# Sensors.net
KiCad netlist of a schematic drawn in Altium Designer
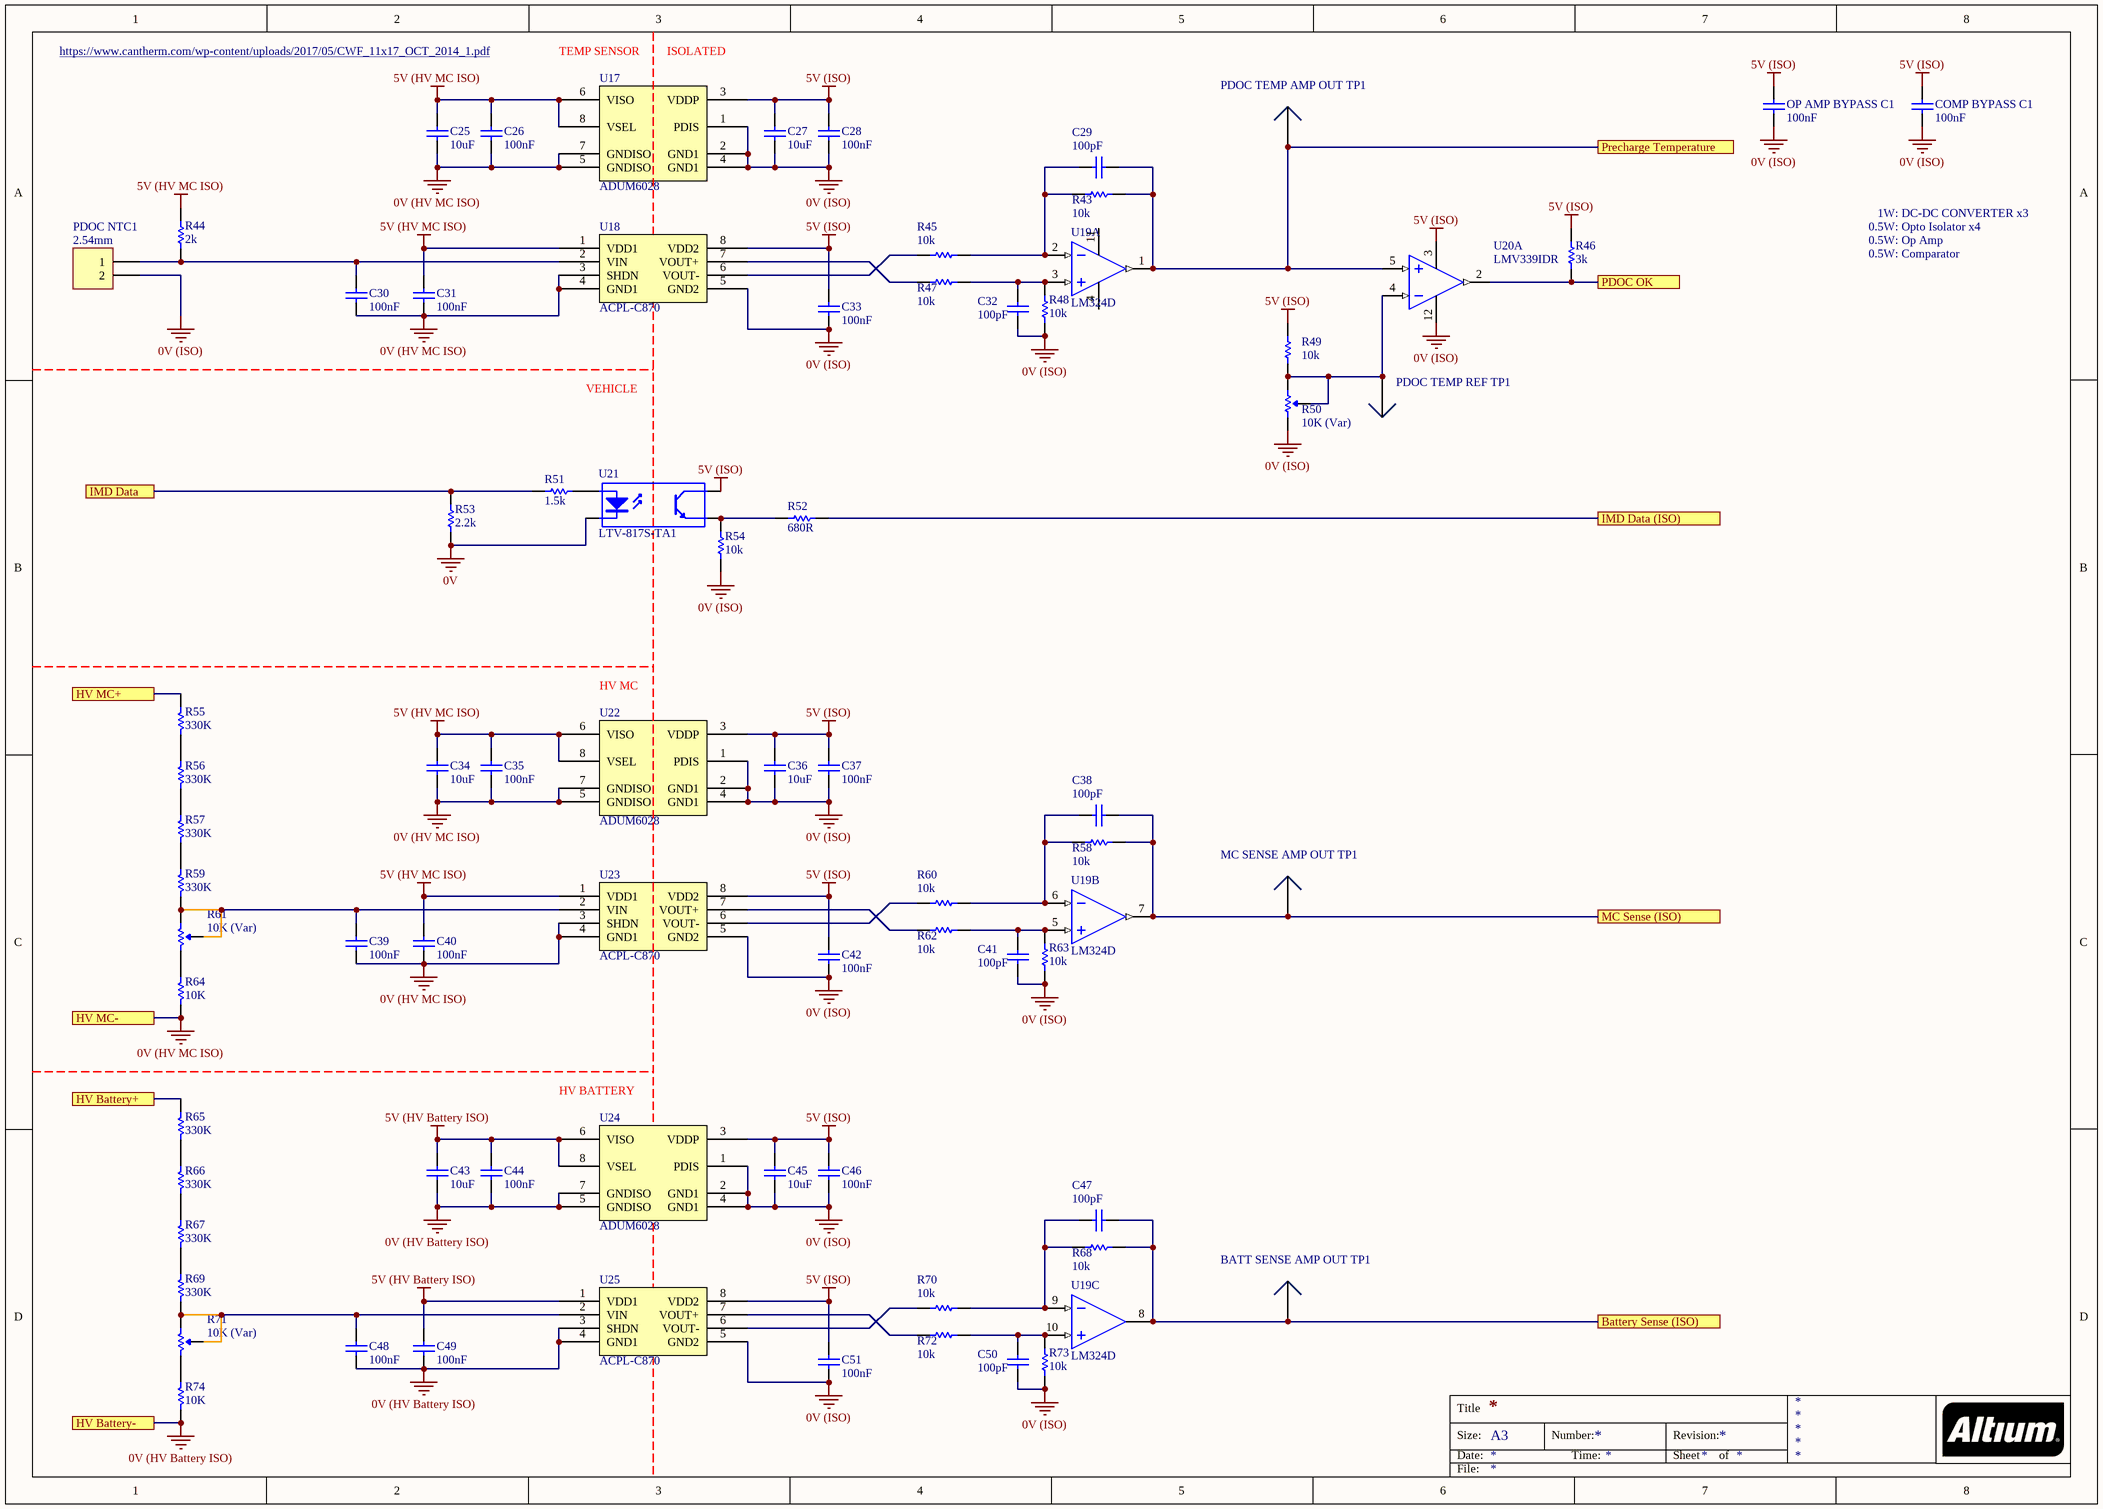
[diagram p0: Sensors.SchDoc]

(export (version "E")
  (design (tool "Eeschema 10.0.6"))
  (components
    (comp (ref "BATT SENSE AMP OUT TP1")
      (value "0mm")
      (footprint "SMD Test Point")
      (fields (field (name "PART NUMBER") "SMD Test Point") (field (name "CONTACT") "NA"))
      (libsource (lib "ts_20-standard-connectors") (part "Test Point"))
    )
    (comp (ref "C25")
      (value "10uF")
      (footprint "0805")
      (fields
        (field (name "PART NUMBER") "GRM21BR6YA106KE43L")
        (field (name "TOLERANCE") "10%")
        (field (name "MANUFACTURER") "muRata")
      )
      (libsource (lib "ts_20-standard-library") (part "Capacitor"))
    )
    (comp (ref "C26")
      (value "100nF")
      (footprint "0805")
      (fields
        (field (name "PART NUMBER") "GCM21BR71E104KA37L")
        (field (name "TOLERANCE") "10%")
        (field (name "MANUFACTURER") "muRata")
      )
      (libsource (lib "ts_20-standard-library") (part "Capacitor"))
    )
    (comp (ref "C27")
      (value "10uF")
      (footprint "0805")
      (fields
        (field (name "PART NUMBER") "GRM21BR6YA106KE43L")
        (field (name "TOLERANCE") "10%")
        (field (name "MANUFACTURER") "muRata")
      )
      (libsource (lib "ts_20-standard-library") (part "Capacitor"))
    )
    (comp (ref "C28")
      (value "100nF")
      (footprint "0805")
      (fields
        (field (name "PART NUMBER") "GCM21BR71E104KA37L")
        (field (name "TOLERANCE") "10%")
        (field (name "MANUFACTURER") "muRata")
      )
      (libsource (lib "ts_20-standard-library") (part "Capacitor"))
    )
    (comp (ref "C29")
      (value "100pF")
      (footprint "0805")
      (fields
        (field (name "PART NUMBER") "GCM21B5C1H101JA37L")
        (field (name "TOLERANCE") "5%")
        (field (name "MANUFACTURER") "muRata")
      )
      (libsource (lib "ts_20-standard-library") (part "Capacitor"))
    )
    (comp (ref "C30")
      (value "100nF")
      (footprint "0805")
      (fields
        (field (name "PART NUMBER") "GCM21BR71E104KA37L")
        (field (name "TOLERANCE") "10%")
        (field (name "MANUFACTURER") "muRata")
      )
      (libsource (lib "ts_20-standard-library") (part "Capacitor"))
    )
    (comp (ref "C31")
      (value "100nF")
      (footprint "0805")
      (fields
        (field (name "PART NUMBER") "GCM21BR71E104KA37L")
        (field (name "TOLERANCE") "10%")
        (field (name "MANUFACTURER") "muRata")
      )
      (libsource (lib "ts_20-standard-library") (part "Capacitor"))
    )
    (comp (ref "C32")
      (value "100pF")
      (footprint "0805")
      (fields
        (field (name "PART NUMBER") "GCM21B5C1H101JA37L")
        (field (name "TOLERANCE") "5%")
        (field (name "MANUFACTURER") "muRata")
      )
      (libsource (lib "ts_20-standard-library") (part "Capacitor"))
    )
    (comp (ref "C33")
      (value "100nF")
      (footprint "0805")
      (fields
        (field (name "PART NUMBER") "GCM21BR71E104KA37L")
        (field (name "TOLERANCE") "10%")
        (field (name "MANUFACTURER") "muRata")
      )
      (libsource (lib "ts_20-standard-library") (part "Capacitor"))
    )
    (comp (ref "C34")
      (value "10uF")
      (footprint "0805")
      (fields
        (field (name "PART NUMBER") "GRM21BR6YA106KE43L")
        (field (name "TOLERANCE") "10%")
        (field (name "MANUFACTURER") "muRata")
      )
      (libsource (lib "ts_20-standard-library") (part "Capacitor"))
    )
    (comp (ref "C35")
      (value "100nF")
      (footprint "0805")
      (fields
        (field (name "PART NUMBER") "GCM21BR71E104KA37L")
        (field (name "TOLERANCE") "10%")
        (field (name "MANUFACTURER") "muRata")
      )
      (libsource (lib "ts_20-standard-library") (part "Capacitor"))
    )
    (comp (ref "C36")
      (value "10uF")
      (footprint "0805")
      (fields
        (field (name "PART NUMBER") "GRM21BR6YA106KE43L")
        (field (name "TOLERANCE") "10%")
        (field (name "MANUFACTURER") "muRata")
      )
      (libsource (lib "ts_20-standard-library") (part "Capacitor"))
    )
    (comp (ref "C37")
      (value "100nF")
      (footprint "0805")
      (fields
        (field (name "PART NUMBER") "GCM21BR71E104KA37L")
        (field (name "TOLERANCE") "10%")
        (field (name "MANUFACTURER") "muRata")
      )
      (libsource (lib "ts_20-standard-library") (part "Capacitor"))
    )
    (comp (ref "C38")
      (value "100pF")
      (footprint "0805")
      (fields
        (field (name "PART NUMBER") "GCM21B5C1H101JA37L")
        (field (name "TOLERANCE") "5%")
        (field (name "MANUFACTURER") "muRata")
      )
      (libsource (lib "ts_20-standard-library") (part "Capacitor"))
    )
    (comp (ref "C39")
      (value "100nF")
      (footprint "0805")
      (fields
        (field (name "PART NUMBER") "GCM21BR71E104KA37L")
        (field (name "TOLERANCE") "10%")
        (field (name "MANUFACTURER") "muRata")
      )
      (libsource (lib "ts_20-standard-library") (part "Capacitor"))
    )
    (comp (ref "C40")
      (value "100nF")
      (footprint "0805")
      (fields
        (field (name "PART NUMBER") "GCM21BR71E104KA37L")
        (field (name "TOLERANCE") "10%")
        (field (name "MANUFACTURER") "muRata")
      )
      (libsource (lib "ts_20-standard-library") (part "Capacitor"))
    )
    (comp (ref "C41")
      (value "100pF")
      (footprint "0805")
      (fields
        (field (name "PART NUMBER") "GCM21B5C1H101JA37L")
        (field (name "TOLERANCE") "5%")
        (field (name "MANUFACTURER") "muRata")
      )
      (libsource (lib "ts_20-standard-library") (part "Capacitor"))
    )
    (comp (ref "C42")
      (value "100nF")
      (footprint "0805")
      (fields
        (field (name "PART NUMBER") "GCM21BR71E104KA37L")
        (field (name "TOLERANCE") "10%")
        (field (name "MANUFACTURER") "muRata")
      )
      (libsource (lib "ts_20-standard-library") (part "Capacitor"))
    )
    (comp (ref "C43")
      (value "10uF")
      (footprint "0805")
      (fields
        (field (name "PART NUMBER") "GRM21BR6YA106KE43L")
        (field (name "TOLERANCE") "10%")
        (field (name "MANUFACTURER") "muRata")
      )
      (libsource (lib "ts_20-standard-library") (part "Capacitor"))
    )
    (comp (ref "C44")
      (value "100nF")
      (footprint "0805")
      (fields
        (field (name "PART NUMBER") "GCM21BR71E104KA37L")
        (field (name "TOLERANCE") "10%")
        (field (name "MANUFACTURER") "muRata")
      )
      (libsource (lib "ts_20-standard-library") (part "Capacitor"))
    )
    (comp (ref "C45")
      (value "10uF")
      (footprint "0805")
      (fields
        (field (name "PART NUMBER") "GRM21BR6YA106KE43L")
        (field (name "TOLERANCE") "10%")
        (field (name "MANUFACTURER") "muRata")
      )
      (libsource (lib "ts_20-standard-library") (part "Capacitor"))
    )
    (comp (ref "C46")
      (value "100nF")
      (footprint "0805")
      (fields
        (field (name "PART NUMBER") "GCM21BR71E104KA37L")
        (field (name "TOLERANCE") "10%")
        (field (name "MANUFACTURER") "muRata")
      )
      (libsource (lib "ts_20-standard-library") (part "Capacitor"))
    )
    (comp (ref "C47")
      (value "100pF")
      (footprint "0805")
      (fields
        (field (name "PART NUMBER") "GCM21B5C1H101JA37L")
        (field (name "TOLERANCE") "5%")
        (field (name "MANUFACTURER") "muRata")
      )
      (libsource (lib "ts_20-standard-library") (part "Capacitor"))
    )
    (comp (ref "C48")
      (value "100nF")
      (footprint "0805")
      (fields
        (field (name "PART NUMBER") "GCM21BR71E104KA37L")
        (field (name "TOLERANCE") "10%")
        (field (name "MANUFACTURER") "muRata")
      )
      (libsource (lib "ts_20-standard-library") (part "Capacitor"))
    )
    (comp (ref "C49")
      (value "100nF")
      (footprint "0805")
      (fields
        (field (name "PART NUMBER") "GCM21BR71E104KA37L")
        (field (name "TOLERANCE") "10%")
        (field (name "MANUFACTURER") "muRata")
      )
      (libsource (lib "ts_20-standard-library") (part "Capacitor"))
    )
    (comp (ref "C50")
      (value "100pF")
      (footprint "0805")
      (fields
        (field (name "PART NUMBER") "GCM21B5C1H101JA37L")
        (field (name "TOLERANCE") "5%")
        (field (name "MANUFACTURER") "muRata")
      )
      (libsource (lib "ts_20-standard-library") (part "Capacitor"))
    )
    (comp (ref "C51")
      (value "100nF")
      (footprint "0805")
      (fields
        (field (name "PART NUMBER") "GCM21BR71E104KA37L")
        (field (name "TOLERANCE") "10%")
        (field (name "MANUFACTURER") "muRata")
      )
      (libsource (lib "ts_20-standard-library") (part "Capacitor"))
    )
    (comp (ref "COMP BYPASS C1")
      (value "100nF")
      (footprint "0805")
      (fields
        (field (name "PART NUMBER") "GCM21BR71E104KA37L")
        (field (name "TOLERANCE") "10%")
        (field (name "MANUFACTURER") "muRata")
      )
      (libsource (lib "ts_20-standard-library") (part "Capacitor"))
    )
    (comp (ref "MC SENSE AMP OUT TP1")
      (value "0mm")
      (footprint "SMD Test Point")
      (fields (field (name "PART NUMBER") "SMD Test Point") (field (name "CONTACT") "NA"))
      (libsource (lib "ts_20-standard-connectors") (part "Test Point"))
    )
    (comp (ref "OP AMP BYPASS C1")
      (value "100nF")
      (footprint "0805")
      (fields
        (field (name "PART NUMBER") "GCM21BR71E104KA37L")
        (field (name "TOLERANCE") "10%")
        (field (name "MANUFACTURER") "muRata")
      )
      (libsource (lib "ts_20-standard-library") (part "Capacitor"))
    )
    (comp (ref "PDOC NTC1")
      (value "2.54mm")
      (footprint "TH 2.54mm Header 1x2")
      (fields (field (name "PART NUMBER") "TH 2.54mm Header 1x2") (field (name "CONTACT") "NA"))
      (libsource (lib "ts_20-standard-connectors") (part "Header 1x2"))
    )
    (comp (ref "PDOC TEMP AMP OUT TP1")
      (value "0mm")
      (footprint "SMD Test Point")
      (fields (field (name "PART NUMBER") "SMD Test Point") (field (name "CONTACT") "NA"))
      (libsource (lib "ts_20-standard-connectors") (part "Test Point"))
    )
    (comp (ref "PDOC TEMP REF TP1")
      (value "0mm")
      (footprint "SMD Test Point")
      (fields (field (name "PART NUMBER") "SMD Test Point") (field (name "CONTACT") "NA"))
      (libsource (lib "ts_20-standard-connectors") (part "Test Point"))
    )
    (comp (ref "R43")
      (value "10k")
      (footprint "0805")
      (fields
        (field (name "PART NUMBER") "RC0805FR0710KL")
        (field (name "MANUFACTURER") "YAGEO")
        (field (name "TOLERANCE") "0.01")
      )
      (libsource (lib "ts_20-standard-library") (part "Resistor"))
    )
    (comp (ref "R44")
      (value "2k")
      (footprint "0805")
      (fields
        (field (name "PART NUMBER") "RC0805FR072KL")
        (field (name "MANUFACTURER") "YAGEO")
        (field (name "TOLERANCE") "0.01")
      )
      (libsource (lib "ts_20-standard-library") (part "Resistor"))
    )
    (comp (ref "R45")
      (value "10k")
      (footprint "0805")
      (fields
        (field (name "PART NUMBER") "RC0805FR0710KL")
        (field (name "MANUFACTURER") "YAGEO")
        (field (name "TOLERANCE") "0.01")
      )
      (libsource (lib "ts_20-standard-library") (part "Resistor"))
    )
    (comp (ref "R46")
      (value "3k")
      (footprint "0805")
      (fields
        (field (name "PART NUMBER") "RC0805FR073KL")
        (field (name "MANUFACTURER") "YAGEO")
        (field (name "TOLERANCE") "0.01")
      )
      (libsource (lib "ts_20-standard-library") (part "Resistor"))
    )
    (comp (ref "R47")
      (value "10k")
      (footprint "0805")
      (fields
        (field (name "PART NUMBER") "RC0805FR0710KL")
        (field (name "MANUFACTURER") "YAGEO")
        (field (name "TOLERANCE") "0.01")
      )
      (libsource (lib "ts_20-standard-library") (part "Resistor"))
    )
    (comp (ref "R48")
      (value "10k")
      (footprint "0805")
      (fields
        (field (name "PART NUMBER") "RC0805FR0710KL")
        (field (name "MANUFACTURER") "YAGEO")
        (field (name "TOLERANCE") "0.01")
      )
      (libsource (lib "ts_20-standard-library") (part "Resistor"))
    )
    (comp (ref "R49")
      (value "10k")
      (footprint "0805")
      (fields
        (field (name "PART NUMBER") "RC0805FR0710KL")
        (field (name "MANUFACTURER") "YAGEO")
        (field (name "TOLERANCE") "0.01")
      )
      (libsource (lib "ts_20-standard-library") (part "Resistor"))
    )
    (comp (ref "R50")
      (value "10K (Var)")
      (footprint "B 3296")
      (fields
        (field (name "PART NUMBER") "3296W-1-103LF")
        (field (name "MANUFACTURER") "Bournes Inc")
        (field (name "TOLERANCE") "0.1")
      )
      (libsource (lib "ts_20-standard-library") (part "Resistor (Potentiometer)"))
    )
    (comp (ref "R51")
      (value "1.5k")
      (footprint "0805")
      (fields
        (field (name "PART NUMBER") "RC0805FR071K5L")
        (field (name "MANUFACTURER") "YAGEO")
        (field (name "TOLERANCE") "0.01")
      )
      (libsource (lib "ts_20-standard-library") (part "Resistor"))
    )
    (comp (ref "R52")
      (value "680R")
      (footprint "0805")
      (fields
        (field (name "PART NUMBER") "RC0805FR07680RL")
        (field (name "MANUFACTURER") "YAGEO")
        (field (name "TOLERANCE") "0.01")
      )
      (libsource (lib "ts_20-standard-library") (part "Resistor"))
    )
    (comp (ref "R53")
      (value "2.2k")
      (footprint "0805")
      (fields
        (field (name "PART NUMBER") "RC0805FR072K2L")
        (field (name "MANUFACTURER") "YAGEO")
        (field (name "TOLERANCE") "0.01")
      )
      (libsource (lib "ts_20-standard-library") (part "Resistor"))
    )
    (comp (ref "R54")
      (value "10k")
      (footprint "0805")
      (fields
        (field (name "PART NUMBER") "RC0805FR0710KL")
        (field (name "MANUFACTURER") "YAGEO")
        (field (name "TOLERANCE") "0.01")
      )
      (libsource (lib "ts_20-standard-library") (part "Resistor"))
    )
    (comp (ref "R55")
      (value "330K")
      (footprint "VB 0207")
      (fields
        (field (name "PART NUMBER") "MMB02070C3303FB200")
        (field (name "MANUFACTURER") "Vishay Beyschlag")
        (field (name "TOLERANCE") "0.01")
      )
      (libsource (lib "ts_20-standard-library") (part "Resistor"))
    )
    (comp (ref "R56")
      (value "330K")
      (footprint "VB 0207")
      (fields
        (field (name "PART NUMBER") "MMB02070C3303FB200")
        (field (name "MANUFACTURER") "Vishay Beyschlag")
        (field (name "TOLERANCE") "0.01")
      )
      (libsource (lib "ts_20-standard-library") (part "Resistor"))
    )
    (comp (ref "R57")
      (value "330K")
      (footprint "VB 0207")
      (fields
        (field (name "PART NUMBER") "MMB02070C3303FB200")
        (field (name "MANUFACTURER") "Vishay Beyschlag")
        (field (name "TOLERANCE") "0.01")
      )
      (libsource (lib "ts_20-standard-library") (part "Resistor"))
    )
    (comp (ref "R58")
      (value "10k")
      (footprint "0805")
      (fields
        (field (name "PART NUMBER") "RC0805FR0710KL")
        (field (name "MANUFACTURER") "YAGEO")
        (field (name "TOLERANCE") "0.01")
      )
      (libsource (lib "ts_20-standard-library") (part "Resistor"))
    )
    (comp (ref "R59")
      (value "330K")
      (footprint "VB 0207")
      (fields
        (field (name "PART NUMBER") "MMB02070C3303FB200")
        (field (name "MANUFACTURER") "Vishay Beyschlag")
        (field (name "TOLERANCE") "0.01")
      )
      (libsource (lib "ts_20-standard-library") (part "Resistor"))
    )
    (comp (ref "R60")
      (value "10k")
      (footprint "0805")
      (fields
        (field (name "PART NUMBER") "RC0805FR0710KL")
        (field (name "MANUFACTURER") "YAGEO")
        (field (name "TOLERANCE") "0.01")
      )
      (libsource (lib "ts_20-standard-library") (part "Resistor"))
    )
    (comp (ref "R61")
      (value "10K (Var)")
      (footprint "B 3296")
      (fields
        (field (name "PART NUMBER") "3296W-1-103LF")
        (field (name "MANUFACTURER") "Bournes Inc")
        (field (name "TOLERANCE") "0.1")
      )
      (libsource (lib "ts_20-standard-library") (part "Resistor (Potentiometer)"))
    )
    (comp (ref "R62")
      (value "10k")
      (footprint "0805")
      (fields
        (field (name "PART NUMBER") "RC0805FR0710KL")
        (field (name "MANUFACTURER") "YAGEO")
        (field (name "TOLERANCE") "0.01")
      )
      (libsource (lib "ts_20-standard-library") (part "Resistor"))
    )
    (comp (ref "R63")
      (value "10k")
      (footprint "0805")
      (fields
        (field (name "PART NUMBER") "RC0805FR0710KL")
        (field (name "MANUFACTURER") "YAGEO")
        (field (name "TOLERANCE") "0.01")
      )
      (libsource (lib "ts_20-standard-library") (part "Resistor"))
    )
    (comp (ref "R64")
      (value "10K")
      (footprint "VB 0207")
      (fields
        (field (name "PART NUMBER") "MMB02070C1002FB200")
        (field (name "MANUFACTURER") "Vishay Beyschlag")
        (field (name "TOLERANCE") "0.01")
      )
      (libsource (lib "ts_20-standard-library") (part "Resistor"))
    )
    (comp (ref "R65")
      (value "330K")
      (footprint "VB 0207")
      (fields
        (field (name "PART NUMBER") "MMB02070C3303FB200")
        (field (name "MANUFACTURER") "Vishay Beyschlag")
        (field (name "TOLERANCE") "0.01")
      )
      (libsource (lib "ts_20-standard-library") (part "Resistor"))
    )
    (comp (ref "R66")
      (value "330K")
      (footprint "VB 0207")
      (fields
        (field (name "PART NUMBER") "MMB02070C3303FB200")
        (field (name "MANUFACTURER") "Vishay Beyschlag")
        (field (name "TOLERANCE") "0.01")
      )
      (libsource (lib "ts_20-standard-library") (part "Resistor"))
    )
    (comp (ref "R67")
      (value "330K")
      (footprint "VB 0207")
      (fields
        (field (name "PART NUMBER") "MMB02070C3303FB200")
        (field (name "MANUFACTURER") "Vishay Beyschlag")
        (field (name "TOLERANCE") "0.01")
      )
      (libsource (lib "ts_20-standard-library") (part "Resistor"))
    )
    (comp (ref "R68")
      (value "10k")
      (footprint "0805")
      (fields
        (field (name "PART NUMBER") "RC0805FR0710KL")
        (field (name "MANUFACTURER") "YAGEO")
        (field (name "TOLERANCE") "0.01")
      )
      (libsource (lib "ts_20-standard-library") (part "Resistor"))
    )
    (comp (ref "R69")
      (value "330K")
      (footprint "VB 0207")
      (fields
        (field (name "PART NUMBER") "MMB02070C3303FB200")
        (field (name "MANUFACTURER") "Vishay Beyschlag")
        (field (name "TOLERANCE") "0.01")
      )
      (libsource (lib "ts_20-standard-library") (part "Resistor"))
    )
    (comp (ref "R70")
      (value "10k")
      (footprint "0805")
      (fields
        (field (name "PART NUMBER") "RC0805FR0710KL")
        (field (name "MANUFACTURER") "YAGEO")
        (field (name "TOLERANCE") "0.01")
      )
      (libsource (lib "ts_20-standard-library") (part "Resistor"))
    )
    (comp (ref "R71")
      (value "10K (Var)")
      (footprint "B 3296")
      (fields
        (field (name "PART NUMBER") "3296W-1-103LF")
        (field (name "MANUFACTURER") "Bournes Inc")
        (field (name "TOLERANCE") "0.1")
      )
      (libsource (lib "ts_20-standard-library") (part "Resistor (Potentiometer)"))
    )
    (comp (ref "R72")
      (value "10k")
      (footprint "0805")
      (fields
        (field (name "PART NUMBER") "RC0805FR0710KL")
        (field (name "MANUFACTURER") "YAGEO")
        (field (name "TOLERANCE") "0.01")
      )
      (libsource (lib "ts_20-standard-library") (part "Resistor"))
    )
    (comp (ref "R73")
      (value "10k")
      (footprint "0805")
      (fields
        (field (name "PART NUMBER") "RC0805FR0710KL")
        (field (name "MANUFACTURER") "YAGEO")
        (field (name "TOLERANCE") "0.01")
      )
      (libsource (lib "ts_20-standard-library") (part "Resistor"))
    )
    (comp (ref "R74")
      (value "10K")
      (footprint "VB 0207")
      (fields
        (field (name "PART NUMBER") "MMB02070C1002FB200")
        (field (name "MANUFACTURER") "Vishay Beyschlag")
        (field (name "TOLERANCE") "0.01")
      )
      (libsource (lib "ts_20-standard-library") (part "Resistor"))
    )
    (comp (ref "U17")
      (value "ADUM6028")
      (footprint "AD 8-SOIC-W")
      (description "Isolated Module DC DC Converter 1 Output 3.3V, 5V 60mA 4.5V - 5.5V Input")
      (fields
        (field (name "MANUFACTURER") "Analog Devices")
        (field (name "DIGIKEY PART NUMBER") "ADUM6028-5BRIZ-ND")
      )
      (libsource (lib "ts_20-standard-library") (part "ADUM6028"))
    )
    (comp (ref "U18")
      (value "ACPL-C870")
      (footprint "BROAD 8-SOIC")
      (description "Isolation Amplifier 1 Circuit Differential 8-SO")
      (fields
        (field (name "MANUFACTURER") "Broadcom Limited")
        (field (name "DIGIKEY PART NUMBER") "516-2578-5-ND")
      )
      (libsource (lib "ts_20-standard-library") (part "ACPL-C870"))
    )
    (comp (ref "U19")
      (value "LM324D")
      (footprint "TI 14-SOIC")
      (description "IC OPAMP GP 4 CIRCUIT 14SOIC")
      (fields
        (field (name "MANUFACTURER") "Texas Instruments")
        (field (name "DIGIKEY PART NUMBER") "296-1390-5-ND")
      )
      (libsource (lib "ts_20-standard-library") (part "LM324D"))
    )
    (comp (ref "U20")
      (value "LMV339IDR")
      (footprint "TI 14-SOIC")
      (description "Comparator General Purpose Open Collector 14-SOIC")
      (fields
        (field (name "MANUFACTURER") "Texas Instruments")
        (field (name "DIGIKEY PART NUMBER") "296-6611-2-ND")
      )
      (libsource (lib "ts_20-standard-library") (part "LMV339IDR"))
    )
    (comp (ref "U21")
      (value "LTV-817S-TA1")
      (footprint "ON 4-SMD")
      (description "35V 50ma Optocoupler (VF=1.2V)")
      (fields
        (field (name "MANUFACTURER") "Lite-On Inc")
        (field (name "DIGIKEY PART NUMBER") "160-1893-2-ND")
      )
      (libsource (lib "ts_20-standard-library") (part "LTV-817S-TA1"))
    )
    (comp (ref "U22")
      (value "ADUM6028")
      (footprint "AD 8-SOIC-W")
      (description "Isolated Module DC DC Converter 1 Output 3.3V, 5V 60mA 4.5V - 5.5V Input")
      (fields
        (field (name "MANUFACTURER") "Analog Devices")
        (field (name "DIGIKEY PART NUMBER") "ADUM6028-5BRIZ-ND")
      )
      (libsource (lib "ts_20-standard-library") (part "ADUM6028"))
    )
    (comp (ref "U23")
      (value "ACPL-C870")
      (footprint "BROAD 8-SOIC")
      (description "Isolation Amplifier 1 Circuit Differential 8-SO")
      (fields
        (field (name "MANUFACTURER") "Broadcom Limited")
        (field (name "DIGIKEY PART NUMBER") "516-2578-5-ND")
      )
      (libsource (lib "ts_20-standard-library") (part "ACPL-C870"))
    )
    (comp (ref "U24")
      (value "ADUM6028")
      (footprint "AD 8-SOIC-W")
      (description "Isolated Module DC DC Converter 1 Output 3.3V, 5V 60mA 4.5V - 5.5V Input")
      (fields
        (field (name "MANUFACTURER") "Analog Devices")
        (field (name "DIGIKEY PART NUMBER") "ADUM6028-5BRIZ-ND")
      )
      (libsource (lib "ts_20-standard-library") (part "ADUM6028"))
    )
    (comp (ref "U25")
      (value "ACPL-C870")
      (footprint "BROAD 8-SOIC")
      (description "Isolation Amplifier 1 Circuit Differential 8-SO")
      (fields
        (field (name "MANUFACTURER") "Broadcom Limited")
        (field (name "DIGIKEY PART NUMBER") "516-2578-5-ND")
      )
      (libsource (lib "ts_20-standard-library") (part "ACPL-C870"))
    )
  )
  (nets
    (net (code "1") (name "/Battery Sense (ISO)") (class "Default")
      (node (ref "BATT SENSE AMP OUT TP1") (pin "1") (pinfunction "1_1") (pintype "passive"))
      (node (ref "C47") (pin "2") (pinfunction "2_2") (pintype "passive"))
      (node (ref "R68") (pin "2") (pinfunction "2_2") (pintype "passive"))
      (node (ref "U19") (pin "8") (pinfunction "3OUT_8") (pintype "passive"))
    )
    (net (code "2") (name "/HV Battery+") (class "Default")
      (node (ref "R65") (pin "2") (pinfunction "2_2") (pintype "passive"))
    )
    (net (code "3") (name "/HV MC+") (class "Default")
      (node (ref "R55") (pin "2") (pinfunction "2_2") (pintype "passive"))
    )
    (net (code "4") (name "/IMD Data") (class "Default")
      (node (ref "R51") (pin "1") (pinfunction "1_1") (pintype "passive"))
      (node (ref "R53") (pin "2") (pinfunction "2_2") (pintype "passive"))
    )
    (net (code "5") (name "/IMD Data (ISO)") (class "Default")
      (node (ref "R52") (pin "2") (pinfunction "2_2") (pintype "passive"))
    )
    (net (code "6") (name "/MC Sense (ISO)") (class "Default")
      (node (ref "C38") (pin "2") (pinfunction "2_2") (pintype "passive"))
      (node (ref "MC SENSE AMP OUT TP1") (pin "1") (pinfunction "1_1") (pintype "passive"))
      (node (ref "R58") (pin "2") (pinfunction "2_2") (pintype "passive"))
      (node (ref "U19") (pin "7") (pinfunction "2OUT_7") (pintype "output"))
    )
    (net (code "7") (name "/PDOC OK") (class "Default")
      (node (ref "R46") (pin "1") (pinfunction "1_1") (pintype "passive"))
      (node (ref "U20") (pin "2") (pinfunction "OUT_A_2") (pintype "output"))
    )
    (net (code "8") (name "/Precharge Temperature") (class "Default")
      (node (ref "C29") (pin "2") (pinfunction "2_2") (pintype "passive"))
      (node (ref "PDOC TEMP AMP OUT TP1") (pin "1") (pinfunction "1_1") (pintype "passive"))
      (node (ref "R43") (pin "2") (pinfunction "2_2") (pintype "passive"))
      (node (ref "U19") (pin "1") (pinfunction "1OUT_1") (pintype "output"))
      (node (ref "U20") (pin "5") (pinfunction "IN_A+_5") (pintype "input"))
    )
    (net (code "9") (name "0V") (class "Default")
      (node (ref "R53") (pin "1") (pinfunction "1_1") (pintype "passive"))
      (node (ref "U21") (pin "2") (pinfunction "K_2") (pintype "passive"))
    )
    (net (code "10") (name "0V (HV Battery ISO)") (class "Default")
      (node (ref "C43") (pin "1") (pinfunction "1_1") (pintype "passive"))
      (node (ref "C44") (pin "1") (pinfunction "1_1") (pintype "passive"))
      (node (ref "C48") (pin "1") (pinfunction "1_1") (pintype "passive"))
      (node (ref "C49") (pin "1") (pinfunction "1_1") (pintype "passive"))
      (node (ref "R74") (pin "1") (pinfunction "1_1") (pintype "passive"))
      (node (ref "U24") (pin "5") (pinfunction "GNDISO_5") (pintype "passive"))
      (node (ref "U24") (pin "7") (pinfunction "GNDISO_7") (pintype "passive"))
      (node (ref "U25") (pin "3") (pinfunction "SHDN_3") (pintype "passive"))
      (node (ref "U25") (pin "4") (pinfunction "GND1_4") (pintype "passive"))
    )
    (net (code "11") (name "0V (HV MC ISO)") (class "Default")
      (node (ref "C25") (pin "1") (pinfunction "1_1") (pintype "passive"))
      (node (ref "C26") (pin "1") (pinfunction "1_1") (pintype "passive"))
      (node (ref "C30") (pin "1") (pinfunction "1_1") (pintype "passive"))
      (node (ref "C31") (pin "1") (pinfunction "1_1") (pintype "passive"))
      (node (ref "C34") (pin "1") (pinfunction "1_1") (pintype "passive"))
      (node (ref "C35") (pin "1") (pinfunction "1_1") (pintype "passive"))
      (node (ref "C39") (pin "1") (pinfunction "1_1") (pintype "passive"))
      (node (ref "C40") (pin "1") (pinfunction "1_1") (pintype "passive"))
      (node (ref "R64") (pin "1") (pinfunction "1_1") (pintype "passive"))
      (node (ref "U17") (pin "5") (pinfunction "GNDISO_5") (pintype "passive"))
      (node (ref "U17") (pin "7") (pinfunction "GNDISO_7") (pintype "passive"))
      (node (ref "U18") (pin "3") (pinfunction "SHDN_3") (pintype "passive"))
      (node (ref "U18") (pin "4") (pinfunction "GND1_4") (pintype "passive"))
      (node (ref "U22") (pin "5") (pinfunction "GNDISO_5") (pintype "passive"))
      (node (ref "U22") (pin "7") (pinfunction "GNDISO_7") (pintype "passive"))
      (node (ref "U23") (pin "3") (pinfunction "SHDN_3") (pintype "passive"))
      (node (ref "U23") (pin "4") (pinfunction "GND1_4") (pintype "passive"))
    )
    (net (code "12") (name "0V (ISO)") (class "Default")
      (node (ref "C27") (pin "1") (pinfunction "1_1") (pintype "passive"))
      (node (ref "C28") (pin "1") (pinfunction "1_1") (pintype "passive"))
      (node (ref "C32") (pin "1") (pinfunction "1_1") (pintype "passive"))
      (node (ref "C33") (pin "1") (pinfunction "1_1") (pintype "passive"))
      (node (ref "C36") (pin "1") (pinfunction "1_1") (pintype "passive"))
      (node (ref "C37") (pin "1") (pinfunction "1_1") (pintype "passive"))
      (node (ref "C41") (pin "1") (pinfunction "1_1") (pintype "passive"))
      (node (ref "C42") (pin "1") (pinfunction "1_1") (pintype "passive"))
      (node (ref "C45") (pin "1") (pinfunction "1_1") (pintype "passive"))
      (node (ref "C46") (pin "1") (pinfunction "1_1") (pintype "passive"))
      (node (ref "C50") (pin "1") (pinfunction "1_1") (pintype "passive"))
      (node (ref "C51") (pin "1") (pinfunction "1_1") (pintype "passive"))
      (node (ref "COMP BYPASS C1") (pin "1") (pinfunction "1_1") (pintype "passive"))
      (node (ref "OP AMP BYPASS C1") (pin "1") (pinfunction "1_1") (pintype "passive"))
      (node (ref "PDOC NTC1") (pin "2") (pinfunction "2_2") (pintype "passive"))
      (node (ref "R48") (pin "1") (pinfunction "1_1") (pintype "passive"))
      (node (ref "R50") (pin "3") (pinfunction "CW_3") (pintype "passive"))
      (node (ref "R54") (pin "1") (pinfunction "1_1") (pintype "passive"))
      (node (ref "R63") (pin "1") (pinfunction "1_1") (pintype "passive"))
      (node (ref "R73") (pin "1") (pinfunction "1_1") (pintype "passive"))
      (node (ref "U17") (pin "1") (pinfunction "PDIS_1") (pintype "passive"))
      (node (ref "U17") (pin "2") (pinfunction "GND1_2") (pintype "passive"))
      (node (ref "U17") (pin "4") (pinfunction "GND1_4") (pintype "passive"))
      (node (ref "U18") (pin "5") (pinfunction "GND2_5") (pintype "passive"))
      (node (ref "U20") (pin "12") (pinfunction "V-_12") (pintype "power_in"))
      (node (ref "U22") (pin "1") (pinfunction "PDIS_1") (pintype "passive"))
      (node (ref "U22") (pin "2") (pinfunction "GND1_2") (pintype "passive"))
      (node (ref "U22") (pin "4") (pinfunction "GND1_4") (pintype "passive"))
      (node (ref "U23") (pin "5") (pinfunction "GND2_5") (pintype "passive"))
      (node (ref "U24") (pin "1") (pinfunction "PDIS_1") (pintype "passive"))
      (node (ref "U24") (pin "2") (pinfunction "GND1_2") (pintype "passive"))
      (node (ref "U24") (pin "4") (pinfunction "GND1_4") (pintype "passive"))
      (node (ref "U25") (pin "5") (pinfunction "GND2_5") (pintype "passive"))
    )
    (net (code "13") (name "5V (HV Battery ISO)") (class "Default")
      (node (ref "C43") (pin "2") (pinfunction "2_2") (pintype "passive"))
      (node (ref "C44") (pin "2") (pinfunction "2_2") (pintype "passive"))
      (node (ref "C49") (pin "2") (pinfunction "2_2") (pintype "passive"))
      (node (ref "U24") (pin "6") (pinfunction "VISO_6") (pintype "passive"))
      (node (ref "U24") (pin "8") (pinfunction "VSEL_8") (pintype "passive"))
      (node (ref "U25") (pin "1") (pinfunction "VDD1_1") (pintype "passive"))
    )
    (net (code "14") (name "5V (HV MC ISO)") (class "Default")
      (node (ref "C25") (pin "2") (pinfunction "2_2") (pintype "passive"))
      (node (ref "C26") (pin "2") (pinfunction "2_2") (pintype "passive"))
      (node (ref "C31") (pin "2") (pinfunction "2_2") (pintype "passive"))
      (node (ref "C34") (pin "2") (pinfunction "2_2") (pintype "passive"))
      (node (ref "C35") (pin "2") (pinfunction "2_2") (pintype "passive"))
      (node (ref "C40") (pin "2") (pinfunction "2_2") (pintype "passive"))
      (node (ref "R44") (pin "2") (pinfunction "2_2") (pintype "passive"))
      (node (ref "U17") (pin "6") (pinfunction "VISO_6") (pintype "passive"))
      (node (ref "U17") (pin "8") (pinfunction "VSEL_8") (pintype "passive"))
      (node (ref "U18") (pin "1") (pinfunction "VDD1_1") (pintype "passive"))
      (node (ref "U22") (pin "6") (pinfunction "VISO_6") (pintype "passive"))
      (node (ref "U22") (pin "8") (pinfunction "VSEL_8") (pintype "passive"))
      (node (ref "U23") (pin "1") (pinfunction "VDD1_1") (pintype "passive"))
    )
    (net (code "15") (name "5V (ISO)") (class "Default")
      (node (ref "C27") (pin "2") (pinfunction "2_2") (pintype "passive"))
      (node (ref "C28") (pin "2") (pinfunction "2_2") (pintype "passive"))
      (node (ref "C33") (pin "2") (pinfunction "2_2") (pintype "passive"))
      (node (ref "C36") (pin "2") (pinfunction "2_2") (pintype "passive"))
      (node (ref "C37") (pin "2") (pinfunction "2_2") (pintype "passive"))
      (node (ref "C42") (pin "2") (pinfunction "2_2") (pintype "passive"))
      (node (ref "C45") (pin "2") (pinfunction "2_2") (pintype "passive"))
      (node (ref "C46") (pin "2") (pinfunction "2_2") (pintype "passive"))
      (node (ref "C51") (pin "2") (pinfunction "2_2") (pintype "passive"))
      (node (ref "COMP BYPASS C1") (pin "2") (pinfunction "2_2") (pintype "passive"))
      (node (ref "OP AMP BYPASS C1") (pin "2") (pinfunction "2_2") (pintype "passive"))
      (node (ref "R46") (pin "2") (pinfunction "2_2") (pintype "passive"))
      (node (ref "R49") (pin "2") (pinfunction "2_2") (pintype "passive"))
      (node (ref "U17") (pin "3") (pinfunction "VDDP_3") (pintype "passive"))
      (node (ref "U18") (pin "8") (pinfunction "VDD2_8") (pintype "passive"))
      (node (ref "U20") (pin "3") (pinfunction "V+_3") (pintype "power_in"))
      (node (ref "U21") (pin "4") (pinfunction "C_4") (pintype "passive"))
      (node (ref "U22") (pin "3") (pinfunction "VDDP_3") (pintype "passive"))
      (node (ref "U23") (pin "8") (pinfunction "VDD2_8") (pintype "passive"))
      (node (ref "U24") (pin "3") (pinfunction "VDDP_3") (pintype "passive"))
      (node (ref "U25") (pin "8") (pinfunction "VDD2_8") (pintype "passive"))
    )
    (net (code "16") (name "Net-(C29-Pad1)") (class "Default")
      (node (ref "C29") (pin "1") (pinfunction "1_1") (pintype "passive"))
      (node (ref "R43") (pin "1") (pinfunction "1_1") (pintype "passive"))
      (node (ref "R45") (pin "2") (pinfunction "2_2") (pintype "passive"))
      (node (ref "U19") (pin "2") (pinfunction "1IN+_2") (pintype "input"))
    )
    (net (code "17") (name "Net-(C32-Pad2)") (class "Default")
      (node (ref "C32") (pin "2") (pinfunction "2_2") (pintype "passive"))
      (node (ref "R47") (pin "2") (pinfunction "2_2") (pintype "passive"))
      (node (ref "R48") (pin "2") (pinfunction "2_2") (pintype "passive"))
      (node (ref "U19") (pin "3") (pinfunction "1IN+_3") (pintype "input"))
    )
    (net (code "18") (name "Net-(R50-CCW)") (class "Default")
      (node (ref "PDOC TEMP REF TP1") (pin "1") (pinfunction "1_1") (pintype "passive"))
      (node (ref "R49") (pin "1") (pinfunction "1_1") (pintype "passive"))
      (node (ref "R50") (pin "1") (pinfunction "CCW_1") (pintype "passive"))
      (node (ref "R50") (pin "2") (pinfunction "Wiper_2") (pintype "passive"))
      (node (ref "U20") (pin "4") (pinfunction "IN_A-_4") (pintype "input"))
    )
    (net (code "19") (name "Net-(R55-Pad1)") (class "Default")
      (node (ref "R55") (pin "1") (pinfunction "1_1") (pintype "passive"))
      (node (ref "R56") (pin "2") (pinfunction "2_2") (pintype "passive"))
    )
    (net (code "20") (name "Net-(R56-Pad1)") (class "Default")
      (node (ref "R56") (pin "1") (pinfunction "1_1") (pintype "passive"))
      (node (ref "R57") (pin "2") (pinfunction "2_2") (pintype "passive"))
    )
    (net (code "21") (name "Net-(R57-Pad1)") (class "Default")
      (node (ref "R57") (pin "1") (pinfunction "1_1") (pintype "passive"))
      (node (ref "R59") (pin "2") (pinfunction "2_2") (pintype "passive"))
    )
    (net (code "22") (name "Net-(R61-CCW)") (class "Default")
      (node (ref "R61") (pin "1") (pinfunction "CCW_1") (pintype "passive"))
      (node (ref "R64") (pin "2") (pinfunction "2_2") (pintype "passive"))
    )
    (net (code "23") (name "Net-(R61-CW)") (class "Default")
      (node (ref "C39") (pin "2") (pinfunction "2_2") (pintype "passive"))
      (node (ref "R59") (pin "1") (pinfunction "1_1") (pintype "passive"))
      (node (ref "R61") (pin "2") (pinfunction "Wiper_2") (pintype "passive"))
      (node (ref "R61") (pin "3") (pinfunction "CW_3") (pintype "passive"))
      (node (ref "U23") (pin "2") (pinfunction "VIN_2") (pintype "passive"))
    )
    (net (code "24") (name "Net-(R65-Pad1)") (class "Default")
      (node (ref "R65") (pin "1") (pinfunction "1_1") (pintype "passive"))
      (node (ref "R66") (pin "2") (pinfunction "2_2") (pintype "passive"))
    )
    (net (code "25") (name "Net-(R66-Pad1)") (class "Default")
      (node (ref "R66") (pin "1") (pinfunction "1_1") (pintype "passive"))
      (node (ref "R67") (pin "2") (pinfunction "2_2") (pintype "passive"))
    )
    (net (code "26") (name "Net-(R67-Pad1)") (class "Default")
      (node (ref "R67") (pin "1") (pinfunction "1_1") (pintype "passive"))
      (node (ref "R69") (pin "2") (pinfunction "2_2") (pintype "passive"))
    )
    (net (code "27") (name "Net-(R71-CCW)") (class "Default")
      (node (ref "R71") (pin "1") (pinfunction "CCW_1") (pintype "passive"))
      (node (ref "R74") (pin "2") (pinfunction "2_2") (pintype "passive"))
    )
    (net (code "28") (name "Net-(R71-CW)") (class "Default")
      (node (ref "C48") (pin "2") (pinfunction "2_2") (pintype "passive"))
      (node (ref "R69") (pin "1") (pinfunction "1_1") (pintype "passive"))
      (node (ref "R71") (pin "2") (pinfunction "Wiper_2") (pintype "passive"))
      (node (ref "R71") (pin "3") (pinfunction "CW_3") (pintype "passive"))
      (node (ref "U25") (pin "2") (pinfunction "VIN_2") (pintype "passive"))
    )
    (net (code "29") (name "Net-(U18-VIN)") (class "Default")
      (node (ref "C30") (pin "2") (pinfunction "2_2") (pintype "passive"))
      (node (ref "PDOC NTC1") (pin "1") (pinfunction "1_1") (pintype "passive"))
      (node (ref "R44") (pin "1") (pinfunction "1_1") (pintype "passive"))
      (node (ref "U18") (pin "2") (pinfunction "VIN_2") (pintype "passive"))
    )
    (net (code "30") (name "Net-(U18-VOUT+)") (class "Default")
      (node (ref "R47") (pin "1") (pinfunction "1_1") (pintype "passive"))
      (node (ref "U18") (pin "7") (pinfunction "VOUT+_7") (pintype "passive"))
    )
    (net (code "31") (name "Net-(U18-VOUT-)") (class "Default")
      (node (ref "R45") (pin "1") (pinfunction "1_1") (pintype "passive"))
      (node (ref "U18") (pin "6") (pinfunction "VOUT-_6") (pintype "passive"))
    )
    (net (code "32") (name "Net-(U19B-2IN+)") (class "Default")
      (node (ref "C41") (pin "2") (pinfunction "2_2") (pintype "passive"))
      (node (ref "R62") (pin "2") (pinfunction "2_2") (pintype "passive"))
      (node (ref "R63") (pin "2") (pinfunction "2_2") (pintype "passive"))
      (node (ref "U19") (pin "5") (pinfunction "2IN+_5") (pintype "input"))
    )
    (net (code "33") (name "Net-(U19B-2IN-)") (class "Default")
      (node (ref "C38") (pin "1") (pinfunction "1_1") (pintype "passive"))
      (node (ref "R58") (pin "1") (pinfunction "1_1") (pintype "passive"))
      (node (ref "R60") (pin "2") (pinfunction "2_2") (pintype "passive"))
      (node (ref "U19") (pin "6") (pinfunction "2IN-_6") (pintype "input"))
    )
    (net (code "34") (name "Net-(U19C-3IN+)") (class "Default")
      (node (ref "C50") (pin "2") (pinfunction "2_2") (pintype "passive"))
      (node (ref "R72") (pin "2") (pinfunction "2_2") (pintype "passive"))
      (node (ref "R73") (pin "2") (pinfunction "2_2") (pintype "passive"))
      (node (ref "U19") (pin "10") (pinfunction "3IN+_10") (pintype "input"))
    )
    (net (code "35") (name "Net-(U19C-3IN-)") (class "Default")
      (node (ref "C47") (pin "1") (pinfunction "1_1") (pintype "passive"))
      (node (ref "R68") (pin "1") (pinfunction "1_1") (pintype "passive"))
      (node (ref "R70") (pin "2") (pinfunction "2_2") (pintype "passive"))
      (node (ref "U19") (pin "9") (pinfunction "3IN-_9") (pintype "input"))
    )
    (net (code "36") (name "Net-(U21-A)") (class "Default")
      (node (ref "R51") (pin "2") (pinfunction "2_2") (pintype "passive"))
      (node (ref "U21") (pin "1") (pinfunction "A_1") (pintype "passive"))
    )
    (net (code "37") (name "Net-(U21-E)") (class "Default")
      (node (ref "R52") (pin "1") (pinfunction "1_1") (pintype "passive"))
      (node (ref "R54") (pin "2") (pinfunction "2_2") (pintype "passive"))
      (node (ref "U21") (pin "3") (pinfunction "E_3") (pintype "passive"))
    )
    (net (code "38") (name "Net-(U23-VOUT+)") (class "Default")
      (node (ref "R62") (pin "1") (pinfunction "1_1") (pintype "passive"))
      (node (ref "U23") (pin "7") (pinfunction "VOUT+_7") (pintype "passive"))
    )
    (net (code "39") (name "Net-(U23-VOUT-)") (class "Default")
      (node (ref "R60") (pin "1") (pinfunction "1_1") (pintype "passive"))
      (node (ref "U23") (pin "6") (pinfunction "VOUT-_6") (pintype "passive"))
    )
    (net (code "40") (name "Net-(U25-VOUT+)") (class "Default")
      (node (ref "R72") (pin "1") (pinfunction "1_1") (pintype "passive"))
      (node (ref "U25") (pin "7") (pinfunction "VOUT+_7") (pintype "passive"))
    )
    (net (code "41") (name "Net-(U25-VOUT-)") (class "Default")
      (node (ref "R70") (pin "1") (pinfunction "1_1") (pintype "passive"))
      (node (ref "U25") (pin "6") (pinfunction "VOUT-_6") (pintype "passive"))
    )
    (net (code "42") (name "unconnected-(U19A-GND-Pad11)") (class "Default")
      (node (ref "U19") (pin "11") (pinfunction "GND_11") (pintype "power_in"))
    )
    (net (code "43") (name "unconnected-(U19A-VCC-Pad4)") (class "Default")
      (node (ref "U19") (pin "4") (pinfunction "VCC_4") (pintype "power_in"))
    )
  )
)
